# sensor_board.net
KiCad netlist of a schematic drawn in EAGLE
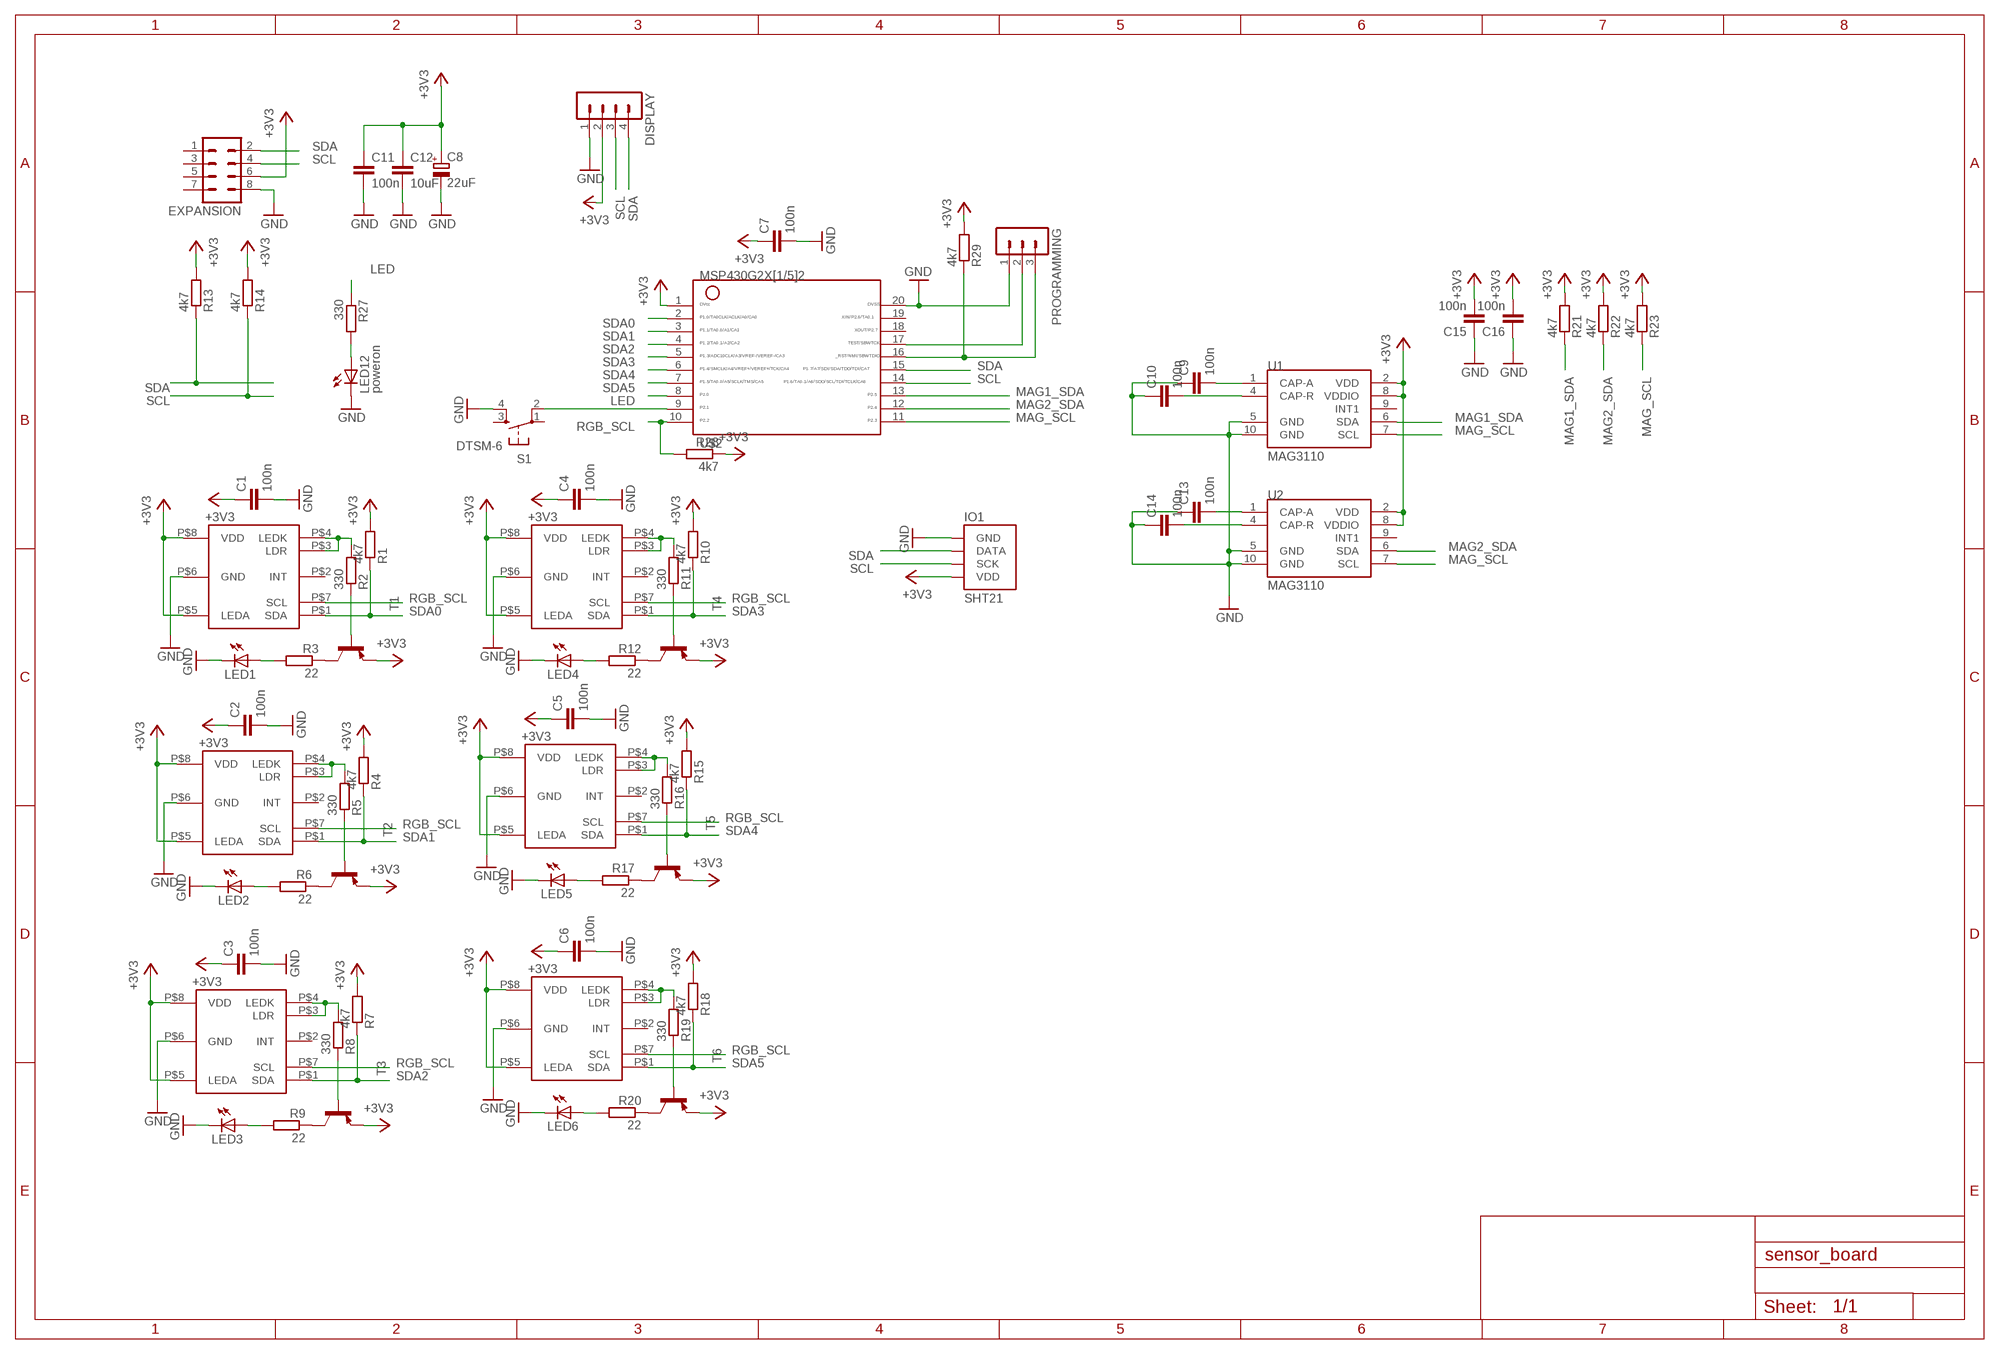
[diagram p0: schematic, sheet 1]

(export (version "E")
  (design (tool "Eeschema 10.0.6"))
  (components
    (comp (ref "C1")
      (value "100n")
      (footprint "eagle-import:C0805")
      (libsource (lib "eagle-import") (part "C-EUC0805"))
    )
    (comp (ref "C2")
      (value "100n")
      (footprint "eagle-import:C0805")
      (libsource (lib "eagle-import") (part "C-EUC0805"))
    )
    (comp (ref "C3")
      (value "100n")
      (footprint "eagle-import:C0805")
      (libsource (lib "eagle-import") (part "C-EUC0805"))
    )
    (comp (ref "C4")
      (value "100n")
      (footprint "eagle-import:C0805")
      (libsource (lib "eagle-import") (part "C-EUC0805"))
    )
    (comp (ref "C5")
      (value "100n")
      (footprint "eagle-import:C0805")
      (libsource (lib "eagle-import") (part "C-EUC0805"))
    )
    (comp (ref "C6")
      (value "100n")
      (footprint "eagle-import:C0805")
      (libsource (lib "eagle-import") (part "C-EUC0805"))
    )
    (comp (ref "C7")
      (value "100n")
      (footprint "eagle-import:C0805")
      (libsource (lib "eagle-import") (part "C-EUC0805"))
    )
    (comp (ref "C8")
      (value "22uF")
      (footprint "eagle-import:153CLV-0505")
      (libsource (lib "eagle-import") (part "CPOL-EU153CLV-0505"))
    )
    (comp (ref "C9")
      (value "100n")
      (footprint "eagle-import:C0805")
      (libsource (lib "eagle-import") (part "C-EUC0805"))
    )
    (comp (ref "C10")
      (value "100n")
      (footprint "eagle-import:C0805")
      (libsource (lib "eagle-import") (part "C-EUC0805"))
    )
    (comp (ref "C11")
      (value "100n")
      (footprint "eagle-import:C0805")
      (libsource (lib "eagle-import") (part "C-EUC0805"))
    )
    (comp (ref "C12")
      (value "10uF")
      (footprint "eagle-import:C0805")
      (libsource (lib "eagle-import") (part "C-EUC0805"))
    )
    (comp (ref "C13")
      (value "100n")
      (footprint "eagle-import:C0805")
      (libsource (lib "eagle-import") (part "C-EUC0805"))
    )
    (comp (ref "C14")
      (value "100n")
      (footprint "eagle-import:C0805")
      (libsource (lib "eagle-import") (part "C-EUC0805"))
    )
    (comp (ref "C15")
      (value "100n")
      (footprint "eagle-import:C0805")
      (libsource (lib "eagle-import") (part "C-EUC0805"))
    )
    (comp (ref "C16")
      (value "100n")
      (footprint "eagle-import:C0805")
      (libsource (lib "eagle-import") (part "C-EUC0805"))
    )
    (comp (ref "DISPLAY")
      (value "MA04-1")
      (footprint "eagle-import:MA04-1")
      (libsource (lib "eagle-import") (part "MA04-1"))
    )
    (comp (ref "EXPANSION")
      (value "MA04-2")
      (footprint "eagle-import:MA04-2")
      (libsource (lib "eagle-import") (part "MA04-2"))
    )
    (comp (ref "IO1")
      (value "SHT21")
      (footprint "eagle-import:SHT2X")
      (libsource (lib "eagle-import") (part "SHT21"))
    )
    (comp (ref "LED1")
      (value "LED5MM")
      (footprint "eagle-import:LED5MM")
      (libsource (lib "eagle-import") (part "my_parts_LED5MM"))
    )
    (comp (ref "LED2")
      (value "LED5MM")
      (footprint "eagle-import:LED5MM")
      (libsource (lib "eagle-import") (part "my_parts_LED5MM"))
    )
    (comp (ref "LED3")
      (value "LED5MM")
      (footprint "eagle-import:LED5MM")
      (libsource (lib "eagle-import") (part "my_parts_LED5MM"))
    )
    (comp (ref "LED4")
      (value "LED5MM")
      (footprint "eagle-import:LED5MM")
      (libsource (lib "eagle-import") (part "my_parts_LED5MM"))
    )
    (comp (ref "LED5")
      (value "LED5MM")
      (footprint "eagle-import:LED5MM")
      (libsource (lib "eagle-import") (part "my_parts_LED5MM"))
    )
    (comp (ref "LED6")
      (value "LED5MM")
      (footprint "eagle-import:LED5MM")
      (libsource (lib "eagle-import") (part "my_parts_LED5MM"))
    )
    (comp (ref "LED12")
      (value "poweron")
      (footprint "eagle-import:CHIPLED_1206")
      (libsource (lib "eagle-import") (part "LEDCHIPLED_1206"))
    )
    (comp (ref "PROGRAMMING")
      (value "MA03-1")
      (footprint "eagle-import:MA03-1")
      (libsource (lib "eagle-import") (part "MA03-1"))
    )
    (comp (ref "R1")
      (value "4k7")
      (footprint "eagle-import:M0805")
      (libsource (lib "eagle-import") (part "R-EU_M0805"))
    )
    (comp (ref "R2")
      (value "330")
      (footprint "eagle-import:M0805")
      (libsource (lib "eagle-import") (part "R-EU_M0805"))
    )
    (comp (ref "R3")
      (value "22")
      (footprint "eagle-import:M0805")
      (libsource (lib "eagle-import") (part "R-EU_M0805"))
    )
    (comp (ref "R4")
      (value "4k7")
      (footprint "eagle-import:M0805")
      (libsource (lib "eagle-import") (part "R-EU_M0805"))
    )
    (comp (ref "R5")
      (value "330")
      (footprint "eagle-import:M0805")
      (libsource (lib "eagle-import") (part "R-EU_M0805"))
    )
    (comp (ref "R6")
      (value "22")
      (footprint "eagle-import:M0805")
      (libsource (lib "eagle-import") (part "R-EU_M0805"))
    )
    (comp (ref "R7")
      (value "4k7")
      (footprint "eagle-import:M0805")
      (libsource (lib "eagle-import") (part "R-EU_M0805"))
    )
    (comp (ref "R8")
      (value "330")
      (footprint "eagle-import:M0805")
      (libsource (lib "eagle-import") (part "R-EU_M0805"))
    )
    (comp (ref "R9")
      (value "22")
      (footprint "eagle-import:M0805")
      (libsource (lib "eagle-import") (part "R-EU_M0805"))
    )
    (comp (ref "R10")
      (value "4k7")
      (footprint "eagle-import:M0805")
      (libsource (lib "eagle-import") (part "R-EU_M0805"))
    )
    (comp (ref "R11")
      (value "330")
      (footprint "eagle-import:M0805")
      (libsource (lib "eagle-import") (part "R-EU_M0805"))
    )
    (comp (ref "R12")
      (value "22")
      (footprint "eagle-import:M0805")
      (libsource (lib "eagle-import") (part "R-EU_M0805"))
    )
    (comp (ref "R13")
      (value "4k7")
      (footprint "eagle-import:M0805")
      (libsource (lib "eagle-import") (part "R-EU_M0805"))
    )
    (comp (ref "R14")
      (value "4k7")
      (footprint "eagle-import:M0805")
      (libsource (lib "eagle-import") (part "R-EU_M0805"))
    )
    (comp (ref "R15")
      (value "4k7")
      (footprint "eagle-import:M0805")
      (libsource (lib "eagle-import") (part "R-EU_M0805"))
    )
    (comp (ref "R16")
      (value "330")
      (footprint "eagle-import:M0805")
      (libsource (lib "eagle-import") (part "R-EU_M0805"))
    )
    (comp (ref "R17")
      (value "22")
      (footprint "eagle-import:M0805")
      (libsource (lib "eagle-import") (part "R-EU_M0805"))
    )
    (comp (ref "R18")
      (value "4k7")
      (footprint "eagle-import:M0805")
      (libsource (lib "eagle-import") (part "R-EU_M0805"))
    )
    (comp (ref "R19")
      (value "330")
      (footprint "eagle-import:M0805")
      (libsource (lib "eagle-import") (part "R-EU_M0805"))
    )
    (comp (ref "R20")
      (value "22")
      (footprint "eagle-import:M0805")
      (libsource (lib "eagle-import") (part "R-EU_M0805"))
    )
    (comp (ref "R21")
      (value "4k7")
      (footprint "eagle-import:M0805")
      (libsource (lib "eagle-import") (part "R-EU_M0805"))
    )
    (comp (ref "R22")
      (value "4k7")
      (footprint "eagle-import:M0805")
      (libsource (lib "eagle-import") (part "R-EU_M0805"))
    )
    (comp (ref "R23")
      (value "4k7")
      (footprint "eagle-import:M0805")
      (libsource (lib "eagle-import") (part "R-EU_M0805"))
    )
    (comp (ref "R27")
      (value "330")
      (footprint "eagle-import:M0805")
      (libsource (lib "eagle-import") (part "R-EU_M0805"))
    )
    (comp (ref "R28")
      (value "4k7")
      (footprint "eagle-import:M0805")
      (libsource (lib "eagle-import") (part "R-EU_M0805"))
    )
    (comp (ref "R29")
      (value "4k7")
      (footprint "eagle-import:M0805")
      (libsource (lib "eagle-import") (part "R-EU_M0805"))
    )
    (comp (ref "S1")
      (value "DTSM-6")
      (footprint "eagle-import:DTSM-6")
      (libsource (lib "eagle-import") (part "DTSM-6"))
    )
    (comp (ref "T1")
      (value "BC857A-PNP-SOT23-BEC")
      (footprint "eagle-import:SOT23-BEC")
      (libsource (lib "eagle-import") (part "-PNP-SOT23-BECBC857A"))
    )
    (comp (ref "T2")
      (value "BC857A-PNP-SOT23-BEC")
      (footprint "eagle-import:SOT23-BEC")
      (libsource (lib "eagle-import") (part "-PNP-SOT23-BECBC857A"))
    )
    (comp (ref "T3")
      (value "BC857A-PNP-SOT23-BEC")
      (footprint "eagle-import:SOT23-BEC")
      (libsource (lib "eagle-import") (part "-PNP-SOT23-BECBC857A"))
    )
    (comp (ref "T4")
      (value "BC857A-PNP-SOT23-BEC")
      (footprint "eagle-import:SOT23-BEC")
      (libsource (lib "eagle-import") (part "-PNP-SOT23-BECBC857A"))
    )
    (comp (ref "T5")
      (value "BC857A-PNP-SOT23-BEC")
      (footprint "eagle-import:SOT23-BEC")
      (libsource (lib "eagle-import") (part "-PNP-SOT23-BECBC857A"))
    )
    (comp (ref "T6")
      (value "BC857A-PNP-SOT23-BEC")
      (footprint "eagle-import:SOT23-BEC")
      (libsource (lib "eagle-import") (part "-PNP-SOT23-BECBC857A"))
    )
    (comp (ref "U$1")
      (value "APDS9950_EDGE")
      (footprint "eagle-import:APDS9950_EDGE")
      (libsource (lib "eagle-import") (part "APDS9950_EDGE"))
    )
    (comp (ref "U$2")
      (value "G2X[1/5]2---PW20")
      (footprint "eagle-import:PW20")
      (libsource (lib "eagle-import") (part "G2X[1/5]2---PW20"))
    )
    (comp (ref "U$3")
      (value "APDS9950_EDGE")
      (footprint "eagle-import:APDS9950_EDGE")
      (libsource (lib "eagle-import") (part "APDS9950_EDGE"))
    )
    (comp (ref "U$4")
      (value "APDS9950_EDGE")
      (footprint "eagle-import:APDS9950_EDGE")
      (libsource (lib "eagle-import") (part "APDS9950_EDGE"))
    )
    (comp (ref "U$5")
      (value "APDS9950_EDGE")
      (footprint "eagle-import:APDS9950_EDGE")
      (libsource (lib "eagle-import") (part "APDS9950_EDGE"))
    )
    (comp (ref "U$6")
      (value "APDS9950_EDGE")
      (footprint "eagle-import:APDS9950_EDGE")
      (libsource (lib "eagle-import") (part "APDS9950_EDGE"))
    )
    (comp (ref "U$7")
      (value "APDS9950_EDGE")
      (footprint "eagle-import:APDS9950_EDGE")
      (libsource (lib "eagle-import") (part "APDS9950_EDGE"))
    )
    (comp (ref "U1")
      (value "MAG3110")
      (footprint "eagle-import:DFN-10")
      (libsource (lib "eagle-import") (part "MAG3110"))
    )
    (comp (ref "U2")
      (value "MAG3110")
      (footprint "eagle-import:DFN-10")
      (libsource (lib "eagle-import") (part "MAG3110"))
    )
  )
  (nets
    (net (code "1") (name "+3V3") (class "Default")
      (node (ref "C1") (pin "1") (pinfunction "1_1") (pintype "passive"))
      (node (ref "C11") (pin "1") (pinfunction "1_1") (pintype "passive"))
      (node (ref "C12") (pin "1") (pinfunction "1_1") (pintype "passive"))
      (node (ref "C15") (pin "2") (pinfunction "2_2") (pintype "passive"))
      (node (ref "C16") (pin "2") (pinfunction "2_2") (pintype "passive"))
      (node (ref "C2") (pin "1") (pinfunction "1_1") (pintype "passive"))
      (node (ref "C3") (pin "1") (pinfunction "1_1") (pintype "passive"))
      (node (ref "C4") (pin "1") (pinfunction "1_1") (pintype "passive"))
      (node (ref "C5") (pin "1") (pinfunction "1_1") (pintype "passive"))
      (node (ref "C6") (pin "1") (pinfunction "1_1") (pintype "passive"))
      (node (ref "C7") (pin "1") (pinfunction "1_1") (pintype "passive"))
      (node (ref "C8") (pin "+") (pinfunction "+_+") (pintype "passive"))
      (node (ref "DISPLAY") (pin "2") (pinfunction "2_2") (pintype "passive"))
      (node (ref "EXPANSION") (pin "6") (pinfunction "6_6") (pintype "passive"))
      (node (ref "IO1") (pin "5") (pinfunction "VDD_5") (pintype "power_in"))
      (node (ref "R1") (pin "2") (pinfunction "2_2") (pintype "passive"))
      (node (ref "R10") (pin "2") (pinfunction "2_2") (pintype "passive"))
      (node (ref "R13") (pin "2") (pinfunction "2_2") (pintype "passive"))
      (node (ref "R14") (pin "2") (pinfunction "2_2") (pintype "passive"))
      (node (ref "R15") (pin "2") (pinfunction "2_2") (pintype "passive"))
      (node (ref "R18") (pin "2") (pinfunction "2_2") (pintype "passive"))
      (node (ref "R21") (pin "2") (pinfunction "2_2") (pintype "passive"))
      (node (ref "R22") (pin "2") (pinfunction "2_2") (pintype "passive"))
      (node (ref "R23") (pin "2") (pinfunction "2_2") (pintype "passive"))
      (node (ref "R28") (pin "1") (pinfunction "1_1") (pintype "passive"))
      (node (ref "R29") (pin "2") (pinfunction "2_2") (pintype "passive"))
      (node (ref "R4") (pin "2") (pinfunction "2_2") (pintype "passive"))
      (node (ref "R7") (pin "2") (pinfunction "2_2") (pintype "passive"))
      (node (ref "T1") (pin "E") (pinfunction "E_E") (pintype "passive"))
      (node (ref "T2") (pin "E") (pinfunction "E_E") (pintype "passive"))
      (node (ref "T3") (pin "E") (pinfunction "E_E") (pintype "passive"))
      (node (ref "T4") (pin "E") (pinfunction "E_E") (pintype "passive"))
      (node (ref "T5") (pin "E") (pinfunction "E_E") (pintype "passive"))
      (node (ref "T6") (pin "E") (pinfunction "E_E") (pintype "passive"))
      (node (ref "U$1") (pin "P$5") (pinfunction "LEDA_P$5") (pintype "bidirectional"))
      (node (ref "U$1") (pin "P$8") (pinfunction "VDD_P$8") (pintype "bidirectional"))
      (node (ref "U$2") (pin "1") (pinfunction "1_1") (pintype "bidirectional"))
      (node (ref "U$3") (pin "P$5") (pinfunction "LEDA_P$5") (pintype "bidirectional"))
      (node (ref "U$3") (pin "P$8") (pinfunction "VDD_P$8") (pintype "bidirectional"))
      (node (ref "U$4") (pin "P$5") (pinfunction "LEDA_P$5") (pintype "bidirectional"))
      (node (ref "U$4") (pin "P$8") (pinfunction "VDD_P$8") (pintype "bidirectional"))
      (node (ref "U$5") (pin "P$5") (pinfunction "LEDA_P$5") (pintype "bidirectional"))
      (node (ref "U$5") (pin "P$8") (pinfunction "VDD_P$8") (pintype "bidirectional"))
      (node (ref "U$6") (pin "P$5") (pinfunction "LEDA_P$5") (pintype "bidirectional"))
      (node (ref "U$6") (pin "P$8") (pinfunction "VDD_P$8") (pintype "bidirectional"))
      (node (ref "U$7") (pin "P$5") (pinfunction "LEDA_P$5") (pintype "bidirectional"))
      (node (ref "U$7") (pin "P$8") (pinfunction "VDD_P$8") (pintype "bidirectional"))
      (node (ref "U1") (pin "2") (pinfunction "VDD_2") (pintype "bidirectional"))
      (node (ref "U1") (pin "8") (pinfunction "VDDIO_8") (pintype "bidirectional"))
      (node (ref "U2") (pin "2") (pinfunction "VDD_2") (pintype "bidirectional"))
      (node (ref "U2") (pin "8") (pinfunction "VDDIO_8") (pintype "bidirectional"))
    )
    (net (code "2") (name "/LED") (class "Default")
      (node (ref "R27") (pin "1") (pinfunction "1_1") (pintype "passive"))
      (node (ref "U$2") (pin "8") (pinfunction "8_8") (pintype "bidirectional"))
    )
    (net (code "3") (name "/MAG1_SDA") (class "Default")
      (node (ref "R21") (pin "1") (pinfunction "1_1") (pintype "passive"))
      (node (ref "U$2") (pin "13") (pinfunction "13_13") (pintype "bidirectional"))
      (node (ref "U1") (pin "6") (pinfunction "SDA_6") (pintype "bidirectional"))
    )
    (net (code "4") (name "/MAG2_SDA") (class "Default")
      (node (ref "R22") (pin "1") (pinfunction "1_1") (pintype "passive"))
      (node (ref "U$2") (pin "12") (pinfunction "12_12") (pintype "bidirectional"))
      (node (ref "U2") (pin "6") (pinfunction "SDA_6") (pintype "bidirectional"))
    )
    (net (code "5") (name "/MAG_SCL") (class "Default")
      (node (ref "R23") (pin "1") (pinfunction "1_1") (pintype "passive"))
      (node (ref "U$2") (pin "11") (pinfunction "11_11") (pintype "bidirectional"))
      (node (ref "U1") (pin "7") (pinfunction "SCL_7") (pintype "bidirectional"))
      (node (ref "U2") (pin "7") (pinfunction "SCL_7") (pintype "bidirectional"))
    )
    (net (code "6") (name "/RGB_SCL") (class "Default")
      (node (ref "R28") (pin "2") (pinfunction "2_2") (pintype "passive"))
      (node (ref "U$1") (pin "P$7") (pinfunction "SCL_P$7") (pintype "bidirectional"))
      (node (ref "U$2") (pin "10") (pinfunction "10_10") (pintype "bidirectional"))
      (node (ref "U$3") (pin "P$7") (pinfunction "SCL_P$7") (pintype "bidirectional"))
      (node (ref "U$4") (pin "P$7") (pinfunction "SCL_P$7") (pintype "bidirectional"))
      (node (ref "U$5") (pin "P$7") (pinfunction "SCL_P$7") (pintype "bidirectional"))
      (node (ref "U$6") (pin "P$7") (pinfunction "SCL_P$7") (pintype "bidirectional"))
      (node (ref "U$7") (pin "P$7") (pinfunction "SCL_P$7") (pintype "bidirectional"))
    )
    (net (code "7") (name "/SCL") (class "Default")
      (node (ref "DISPLAY") (pin "3") (pinfunction "3_3") (pintype "passive"))
      (node (ref "EXPANSION") (pin "4") (pinfunction "4_4") (pintype "passive"))
      (node (ref "IO1") (pin "4") (pinfunction "SCK_4") (pintype "input"))
      (node (ref "R14") (pin "1") (pinfunction "1_1") (pintype "passive"))
      (node (ref "U$2") (pin "14") (pinfunction "14_14") (pintype "bidirectional"))
    )
    (net (code "8") (name "/SDA") (class "Default")
      (node (ref "DISPLAY") (pin "4") (pinfunction "4_4") (pintype "passive"))
      (node (ref "EXPANSION") (pin "2") (pinfunction "2_2") (pintype "passive"))
      (node (ref "IO1") (pin "1") (pinfunction "DATA_1") (pintype "bidirectional"))
      (node (ref "R13") (pin "1") (pinfunction "1_1") (pintype "passive"))
      (node (ref "U$2") (pin "15") (pinfunction "15_15") (pintype "bidirectional"))
    )
    (net (code "9") (name "/SDA0") (class "Default")
      (node (ref "R1") (pin "1") (pinfunction "1_1") (pintype "passive"))
      (node (ref "U$1") (pin "P$1") (pinfunction "SDA_P$1") (pintype "bidirectional"))
      (node (ref "U$2") (pin "2") (pinfunction "2_2") (pintype "bidirectional"))
    )
    (net (code "10") (name "/SDA1") (class "Default")
      (node (ref "R4") (pin "1") (pinfunction "1_1") (pintype "passive"))
      (node (ref "U$2") (pin "3") (pinfunction "3_3") (pintype "bidirectional"))
      (node (ref "U$3") (pin "P$1") (pinfunction "SDA_P$1") (pintype "bidirectional"))
    )
    (net (code "11") (name "/SDA2") (class "Default")
      (node (ref "R7") (pin "1") (pinfunction "1_1") (pintype "passive"))
      (node (ref "U$2") (pin "4") (pinfunction "4_4") (pintype "bidirectional"))
      (node (ref "U$4") (pin "P$1") (pinfunction "SDA_P$1") (pintype "bidirectional"))
    )
    (net (code "12") (name "/SDA3") (class "Default")
      (node (ref "R10") (pin "1") (pinfunction "1_1") (pintype "passive"))
      (node (ref "U$2") (pin "5") (pinfunction "5_5") (pintype "bidirectional"))
      (node (ref "U$5") (pin "P$1") (pinfunction "SDA_P$1") (pintype "bidirectional"))
    )
    (net (code "13") (name "/SDA4") (class "Default")
      (node (ref "R15") (pin "1") (pinfunction "1_1") (pintype "passive"))
      (node (ref "U$2") (pin "6") (pinfunction "6_6") (pintype "bidirectional"))
      (node (ref "U$6") (pin "P$1") (pinfunction "SDA_P$1") (pintype "bidirectional"))
    )
    (net (code "14") (name "/SDA5") (class "Default")
      (node (ref "R18") (pin "1") (pinfunction "1_1") (pintype "passive"))
      (node (ref "U$2") (pin "7") (pinfunction "7_7") (pintype "bidirectional"))
      (node (ref "U$7") (pin "P$1") (pinfunction "SDA_P$1") (pintype "bidirectional"))
    )
    (net (code "15") (name "GND") (class "Default")
      (node (ref "C1") (pin "2") (pinfunction "2_2") (pintype "passive"))
      (node (ref "C10") (pin "1") (pinfunction "1_1") (pintype "passive"))
      (node (ref "C11") (pin "2") (pinfunction "2_2") (pintype "passive"))
      (node (ref "C12") (pin "2") (pinfunction "2_2") (pintype "passive"))
      (node (ref "C13") (pin "1") (pinfunction "1_1") (pintype "passive"))
      (node (ref "C14") (pin "1") (pinfunction "1_1") (pintype "passive"))
      (node (ref "C15") (pin "1") (pinfunction "1_1") (pintype "passive"))
      (node (ref "C16") (pin "1") (pinfunction "1_1") (pintype "passive"))
      (node (ref "C2") (pin "2") (pinfunction "2_2") (pintype "passive"))
      (node (ref "C3") (pin "2") (pinfunction "2_2") (pintype "passive"))
      (node (ref "C4") (pin "2") (pinfunction "2_2") (pintype "passive"))
      (node (ref "C5") (pin "2") (pinfunction "2_2") (pintype "passive"))
      (node (ref "C6") (pin "2") (pinfunction "2_2") (pintype "passive"))
      (node (ref "C7") (pin "2") (pinfunction "2_2") (pintype "passive"))
      (node (ref "C8") (pin "-") (pinfunction "-_-") (pintype "passive"))
      (node (ref "C9") (pin "1") (pinfunction "1_1") (pintype "passive"))
      (node (ref "DISPLAY") (pin "1") (pinfunction "1_1") (pintype "passive"))
      (node (ref "EXPANSION") (pin "8") (pinfunction "8_8") (pintype "passive"))
      (node (ref "IO1") (pin "2") (pinfunction "GND_2") (pintype "power_in"))
      (node (ref "LED1") (pin "K") (pinfunction "C_K") (pintype "passive"))
      (node (ref "LED12") (pin "C") (pinfunction "C_C") (pintype "passive"))
      (node (ref "LED2") (pin "K") (pinfunction "C_K") (pintype "passive"))
      (node (ref "LED3") (pin "K") (pinfunction "C_K") (pintype "passive"))
      (node (ref "LED4") (pin "K") (pinfunction "C_K") (pintype "passive"))
      (node (ref "LED5") (pin "K") (pinfunction "C_K") (pintype "passive"))
      (node (ref "LED6") (pin "K") (pinfunction "C_K") (pintype "passive"))
      (node (ref "PROGRAMMING") (pin "1") (pinfunction "1_1") (pintype "passive"))
      (node (ref "S1") (pin "4") (pinfunction "4_4") (pintype "passive"))
      (node (ref "U$1") (pin "P$6") (pinfunction "GND_P$6") (pintype "bidirectional"))
      (node (ref "U$2") (pin "20") (pinfunction "20_20") (pintype "bidirectional"))
      (node (ref "U$3") (pin "P$6") (pinfunction "GND_P$6") (pintype "bidirectional"))
      (node (ref "U$4") (pin "P$6") (pinfunction "GND_P$6") (pintype "bidirectional"))
      (node (ref "U$5") (pin "P$6") (pinfunction "GND_P$6") (pintype "bidirectional"))
      (node (ref "U$6") (pin "P$6") (pinfunction "GND_P$6") (pintype "bidirectional"))
      (node (ref "U$7") (pin "P$6") (pinfunction "GND_P$6") (pintype "bidirectional"))
      (node (ref "U1") (pin "10") (pinfunction "GND_10") (pintype "bidirectional"))
      (node (ref "U1") (pin "5") (pinfunction "GND_5") (pintype "bidirectional"))
      (node (ref "U2") (pin "10") (pinfunction "GND_10") (pintype "bidirectional"))
      (node (ref "U2") (pin "5") (pinfunction "GND_5") (pintype "bidirectional"))
    )
    (net (code "16") (name "Net-(LED1-PadA)") (class "Default")
      (node (ref "LED1") (pin "A") (pinfunction "A_A") (pintype "passive"))
      (node (ref "R3") (pin "2") (pinfunction "2_2") (pintype "passive"))
    )
    (net (code "17") (name "Net-(LED2-PadA)") (class "Default")
      (node (ref "LED2") (pin "A") (pinfunction "A_A") (pintype "passive"))
      (node (ref "R6") (pin "2") (pinfunction "2_2") (pintype "passive"))
    )
    (net (code "18") (name "Net-(LED3-PadA)") (class "Default")
      (node (ref "LED3") (pin "A") (pinfunction "A_A") (pintype "passive"))
      (node (ref "R9") (pin "2") (pinfunction "2_2") (pintype "passive"))
    )
    (net (code "19") (name "Net-(LED4-PadA)") (class "Default")
      (node (ref "LED4") (pin "A") (pinfunction "A_A") (pintype "passive"))
      (node (ref "R12") (pin "2") (pinfunction "2_2") (pintype "passive"))
    )
    (net (code "20") (name "Net-(LED5-PadA)") (class "Default")
      (node (ref "LED5") (pin "A") (pinfunction "A_A") (pintype "passive"))
      (node (ref "R17") (pin "2") (pinfunction "2_2") (pintype "passive"))
    )
    (net (code "21") (name "Net-(LED6-PadA)") (class "Default")
      (node (ref "LED6") (pin "A") (pinfunction "A_A") (pintype "passive"))
      (node (ref "R20") (pin "2") (pinfunction "2_2") (pintype "passive"))
    )
    (net (code "22") (name "Net-(LED12-PadA)") (class "Default")
      (node (ref "LED12") (pin "A") (pinfunction "A_A") (pintype "passive"))
      (node (ref "R27") (pin "2") (pinfunction "2_2") (pintype "passive"))
    )
    (net (code "23") (name "Net-(PROGRAMMING-Pad2)") (class "Default")
      (node (ref "PROGRAMMING") (pin "2") (pinfunction "2_2") (pintype "passive"))
      (node (ref "U$2") (pin "17") (pinfunction "17_17") (pintype "bidirectional"))
    )
    (net (code "24") (name "Net-(PROGRAMMING-Pad3)") (class "Default")
      (node (ref "PROGRAMMING") (pin "3") (pinfunction "3_3") (pintype "passive"))
      (node (ref "R29") (pin "1") (pinfunction "1_1") (pintype "passive"))
      (node (ref "U$2") (pin "16") (pinfunction "16_16") (pintype "bidirectional"))
    )
    (net (code "25") (name "Net-(R2-Pad1)") (class "Default")
      (node (ref "R2") (pin "1") (pinfunction "1_1") (pintype "passive"))
      (node (ref "T1") (pin "B") (pinfunction "B_B") (pintype "passive"))
    )
    (net (code "26") (name "Net-(R3-Pad1)") (class "Default")
      (node (ref "R3") (pin "1") (pinfunction "1_1") (pintype "passive"))
      (node (ref "T1") (pin "C") (pinfunction "C_C") (pintype "passive"))
    )
    (net (code "27") (name "Net-(R5-Pad1)") (class "Default")
      (node (ref "R5") (pin "1") (pinfunction "1_1") (pintype "passive"))
      (node (ref "T2") (pin "B") (pinfunction "B_B") (pintype "passive"))
    )
    (net (code "28") (name "Net-(R6-Pad1)") (class "Default")
      (node (ref "R6") (pin "1") (pinfunction "1_1") (pintype "passive"))
      (node (ref "T2") (pin "C") (pinfunction "C_C") (pintype "passive"))
    )
    (net (code "29") (name "Net-(R8-Pad1)") (class "Default")
      (node (ref "R8") (pin "1") (pinfunction "1_1") (pintype "passive"))
      (node (ref "T3") (pin "B") (pinfunction "B_B") (pintype "passive"))
    )
    (net (code "30") (name "Net-(R9-Pad1)") (class "Default")
      (node (ref "R9") (pin "1") (pinfunction "1_1") (pintype "passive"))
      (node (ref "T3") (pin "C") (pinfunction "C_C") (pintype "passive"))
    )
    (net (code "31") (name "Net-(R11-Pad1)") (class "Default")
      (node (ref "R11") (pin "1") (pinfunction "1_1") (pintype "passive"))
      (node (ref "T4") (pin "B") (pinfunction "B_B") (pintype "passive"))
    )
    (net (code "32") (name "Net-(R12-Pad1)") (class "Default")
      (node (ref "R12") (pin "1") (pinfunction "1_1") (pintype "passive"))
      (node (ref "T4") (pin "C") (pinfunction "C_C") (pintype "passive"))
    )
    (net (code "33") (name "Net-(R16-Pad1)") (class "Default")
      (node (ref "R16") (pin "1") (pinfunction "1_1") (pintype "passive"))
      (node (ref "T5") (pin "B") (pinfunction "B_B") (pintype "passive"))
    )
    (net (code "34") (name "Net-(R17-Pad1)") (class "Default")
      (node (ref "R17") (pin "1") (pinfunction "1_1") (pintype "passive"))
      (node (ref "T5") (pin "C") (pinfunction "C_C") (pintype "passive"))
    )
    (net (code "35") (name "Net-(R19-Pad1)") (class "Default")
      (node (ref "R19") (pin "1") (pinfunction "1_1") (pintype "passive"))
      (node (ref "T6") (pin "B") (pinfunction "B_B") (pintype "passive"))
    )
    (net (code "36") (name "Net-(R20-Pad1)") (class "Default")
      (node (ref "R20") (pin "1") (pinfunction "1_1") (pintype "passive"))
      (node (ref "T6") (pin "C") (pinfunction "C_C") (pintype "passive"))
    )
    (net (code "37") (name "Net-(S1-Pad2)") (class "Default")
      (node (ref "S1") (pin "2") (pinfunction "2_2") (pintype "passive"))
      (node (ref "U$2") (pin "9") (pinfunction "9_9") (pintype "bidirectional"))
    )
    (net (code "38") (name "Net-(U$1-LDR)") (class "Default")
      (node (ref "R2") (pin "2") (pinfunction "2_2") (pintype "passive"))
      (node (ref "U$1") (pin "P$3") (pinfunction "LDR_P$3") (pintype "bidirectional"))
      (node (ref "U$1") (pin "P$4") (pinfunction "LEDK_P$4") (pintype "bidirectional"))
    )
    (net (code "39") (name "Net-(U$3-LDR)") (class "Default")
      (node (ref "R5") (pin "2") (pinfunction "2_2") (pintype "passive"))
      (node (ref "U$3") (pin "P$3") (pinfunction "LDR_P$3") (pintype "bidirectional"))
      (node (ref "U$3") (pin "P$4") (pinfunction "LEDK_P$4") (pintype "bidirectional"))
    )
    (net (code "40") (name "Net-(U$4-LDR)") (class "Default")
      (node (ref "R8") (pin "2") (pinfunction "2_2") (pintype "passive"))
      (node (ref "U$4") (pin "P$3") (pinfunction "LDR_P$3") (pintype "bidirectional"))
      (node (ref "U$4") (pin "P$4") (pinfunction "LEDK_P$4") (pintype "bidirectional"))
    )
    (net (code "41") (name "Net-(U$5-LDR)") (class "Default")
      (node (ref "R11") (pin "2") (pinfunction "2_2") (pintype "passive"))
      (node (ref "U$5") (pin "P$3") (pinfunction "LDR_P$3") (pintype "bidirectional"))
      (node (ref "U$5") (pin "P$4") (pinfunction "LEDK_P$4") (pintype "bidirectional"))
    )
    (net (code "42") (name "Net-(U$6-LDR)") (class "Default")
      (node (ref "R16") (pin "2") (pinfunction "2_2") (pintype "passive"))
      (node (ref "U$6") (pin "P$3") (pinfunction "LDR_P$3") (pintype "bidirectional"))
      (node (ref "U$6") (pin "P$4") (pinfunction "LEDK_P$4") (pintype "bidirectional"))
    )
    (net (code "43") (name "Net-(U$7-LDR)") (class "Default")
      (node (ref "R19") (pin "2") (pinfunction "2_2") (pintype "passive"))
      (node (ref "U$7") (pin "P$3") (pinfunction "LDR_P$3") (pintype "bidirectional"))
      (node (ref "U$7") (pin "P$4") (pinfunction "LEDK_P$4") (pintype "bidirectional"))
    )
    (net (code "44") (name "Net-(U1-CAP-A)") (class "Default")
      (node (ref "C9") (pin "2") (pinfunction "2_2") (pintype "passive"))
      (node (ref "U1") (pin "1") (pinfunction "CAP-A_1") (pintype "bidirectional"))
    )
    (net (code "45") (name "Net-(U1-CAP-R)") (class "Default")
      (node (ref "C10") (pin "2") (pinfunction "2_2") (pintype "passive"))
      (node (ref "U1") (pin "4") (pinfunction "CAP-R_4") (pintype "bidirectional"))
    )
    (net (code "46") (name "Net-(U2-CAP-A)") (class "Default")
      (node (ref "C13") (pin "2") (pinfunction "2_2") (pintype "passive"))
      (node (ref "U2") (pin "1") (pinfunction "CAP-A_1") (pintype "bidirectional"))
    )
    (net (code "47") (name "Net-(U2-CAP-R)") (class "Default")
      (node (ref "C14") (pin "2") (pinfunction "2_2") (pintype "passive"))
      (node (ref "U2") (pin "4") (pinfunction "CAP-R_4") (pintype "bidirectional"))
    )
    (net (code "48") (name "unconnected-(EXPANSION-Pad1)") (class "Default")
      (node (ref "EXPANSION") (pin "1") (pinfunction "1_1") (pintype "passive"))
    )
    (net (code "49") (name "unconnected-(EXPANSION-Pad3)") (class "Default")
      (node (ref "EXPANSION") (pin "3") (pinfunction "3_3") (pintype "passive"))
    )
    (net (code "50") (name "unconnected-(EXPANSION-Pad5)") (class "Default")
      (node (ref "EXPANSION") (pin "5") (pinfunction "5_5") (pintype "passive"))
    )
    (net (code "51") (name "unconnected-(EXPANSION-Pad7)") (class "Default")
      (node (ref "EXPANSION") (pin "7") (pinfunction "7_7") (pintype "passive"))
    )
    (net (code "52") (name "unconnected-(S1-Pad1)") (class "Default")
      (node (ref "S1") (pin "1") (pinfunction "1_1") (pintype "passive"))
    )
    (net (code "53") (name "unconnected-(S1-Pad3)") (class "Default")
      (node (ref "S1") (pin "3") (pinfunction "3_3") (pintype "passive"))
    )
    (net (code "54") (name "unconnected-(U$1-INT-PadP$2)") (class "Default")
      (node (ref "U$1") (pin "P$2") (pinfunction "INT_P$2") (pintype "bidirectional"))
    )
    (net (code "55") (name "unconnected-(U$2-Pad18)") (class "Default")
      (node (ref "U$2") (pin "18") (pinfunction "18_18") (pintype "bidirectional"))
    )
    (net (code "56") (name "unconnected-(U$2-Pad19)") (class "Default")
      (node (ref "U$2") (pin "19") (pinfunction "19_19") (pintype "bidirectional"))
    )
    (net (code "57") (name "unconnected-(U$3-INT-PadP$2)") (class "Default")
      (node (ref "U$3") (pin "P$2") (pinfunction "INT_P$2") (pintype "bidirectional"))
    )
    (net (code "58") (name "unconnected-(U$4-INT-PadP$2)") (class "Default")
      (node (ref "U$4") (pin "P$2") (pinfunction "INT_P$2") (pintype "bidirectional"))
    )
    (net (code "59") (name "unconnected-(U$5-INT-PadP$2)") (class "Default")
      (node (ref "U$5") (pin "P$2") (pinfunction "INT_P$2") (pintype "bidirectional"))
    )
    (net (code "60") (name "unconnected-(U$6-INT-PadP$2)") (class "Default")
      (node (ref "U$6") (pin "P$2") (pinfunction "INT_P$2") (pintype "bidirectional"))
    )
    (net (code "61") (name "unconnected-(U$7-INT-PadP$2)") (class "Default")
      (node (ref "U$7") (pin "P$2") (pinfunction "INT_P$2") (pintype "bidirectional"))
    )
    (net (code "62") (name "unconnected-(U1-INT1-Pad9)") (class "Default")
      (node (ref "U1") (pin "9") (pinfunction "INT1_9") (pintype "bidirectional"))
    )
    (net (code "63") (name "unconnected-(U2-INT1-Pad9)") (class "Default")
      (node (ref "U2") (pin "9") (pinfunction "INT1_9") (pintype "bidirectional"))
    )
  )
)
